# MCU.net
KiCad netlist of a schematic drawn in Altium Designer
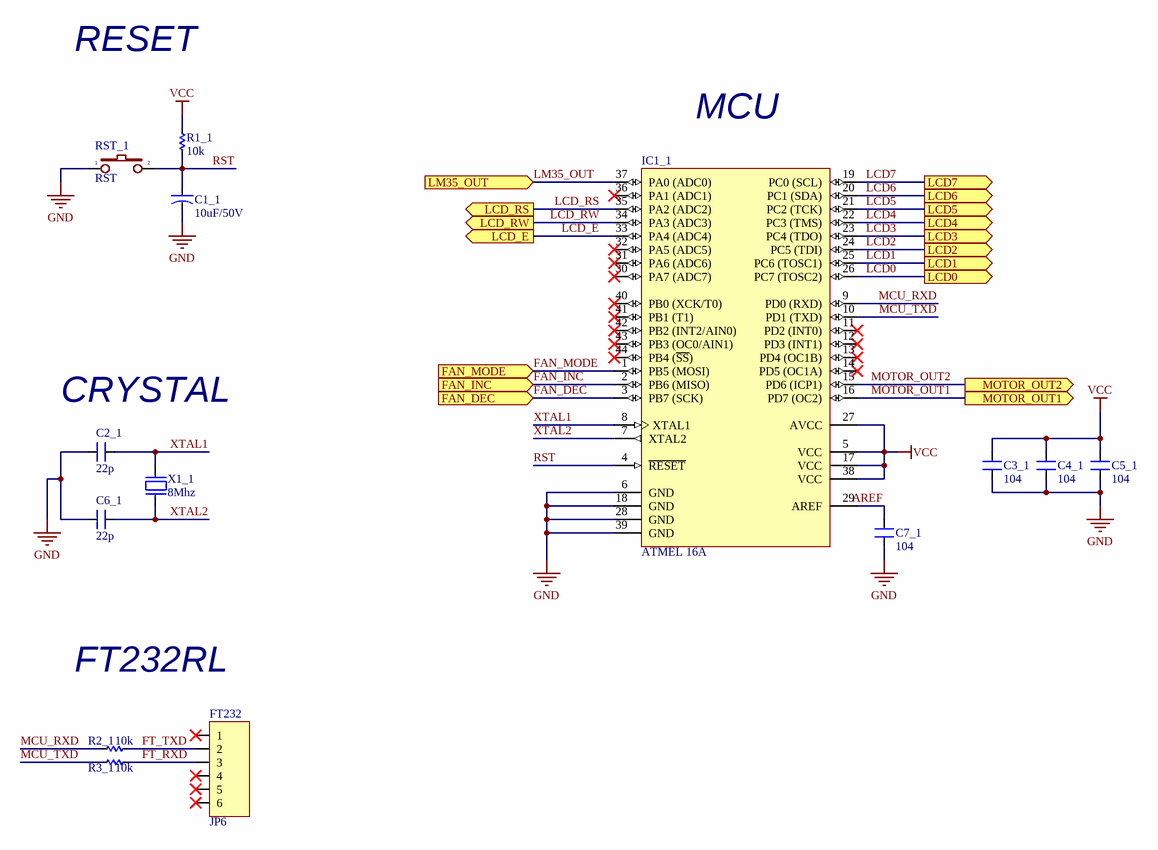
[diagram p0: MCU.SchDoc]

(export (version "E")
  (design (tool "Eeschema 10.0.6"))
  (components
    (comp (ref "C1_1")
      (value "10uF/50V")
      (footprint "CAP-ALU-SMD-5.5x5.5")
      (description "Polarized Capacitor (Axial)")
      (fields (field (name "PUBLISHER") "Altium Limited"))
      (libsource (lib "Altium Library") (part "CN-ALU-SMD"))
    )
    (comp (ref "C2_1") (value "22p") (footprint "CN-SMD-0805") (libsource (lib "Altium Library") (part "CN")))
    (comp (ref "C3_1") (value "104") (footprint "CN-SMD-0805") (libsource (lib "Altium Library") (part "CN")))
    (comp (ref "C4_1") (value "104") (footprint "CN-SMD-0805") (libsource (lib "Altium Library") (part "CN")))
    (comp (ref "C5_1") (value "104") (footprint "CN-SMD-0805") (libsource (lib "Altium Library") (part "CN")))
    (comp (ref "C6_1") (value "22p") (footprint "CN-SMD-0805") (libsource (lib "Altium Library") (part "CN")))
    (comp (ref "C7_1") (value "104") (footprint "CN-SMD-0805") (libsource (lib "Altium Library") (part "CN")))
    (comp (ref "FT232")
      (value "JP6")
      (footprint "JP6-C1T")
      (description "WR-PHD 2.54 mm Angled Socket Header")
      (fields
        (field (name "MANUFACTURER") "Würth Elektronik eiSos GmbH")
        (field (name "PARTNO") "613006143121")
        (field (name "CREATED BY") "Karrer Zheng")
      )
      (libsource (lib "Altium Library") (part "JP6"))
    )
    (comp (ref "IC1_1")
      (value "ATMEL 16A")
      (footprint "TQFP44")
      (libsource (lib "Altium Library") (part "ATmega16A-AU"))
    )
    (comp (ref "R1_1")
      (value "10k")
      (footprint "RES-SMD-0805")
      (description "Resistor")
      (fields
        (field (name "MANUFACTURER") "Generic Components")
        (field (name "PUBLISHER") "Altium Hobart Technology Centre")
      )
      (libsource (lib "Altium Library") (part "Res-SMD"))
    )
    (comp (ref "R2_1")
      (value "10k")
      (footprint "RES-SMD-0805")
      (description "Resistor")
      (fields
        (field (name "MANUFACTURER") "Generic Components")
        (field (name "PUBLISHER") "Altium Hobart Technology Centre")
      )
      (libsource (lib "Altium Library") (part "Res-SMD"))
    )
    (comp (ref "R3_1")
      (value "10k")
      (footprint "RES-SMD-0805")
      (description "Resistor")
      (fields
        (field (name "MANUFACTURER") "Generic Components")
        (field (name "PUBLISHER") "Altium Hobart Technology Centre")
      )
      (libsource (lib "Altium Library") (part "Res-SMD"))
    )
    (comp (ref "RST_1")
      (value "RST")
      (footprint "SW1-SMD")
      (description "Switch button 2 pin")
      (libsource (lib "Altium Library") (part "SW2"))
    )
    (comp (ref "X1_1")
      (value "8Mhz")
      (footprint "XT2")
      (description "Crystal, 32.768 KHz, -40 to 85 degC, 3.2 x 1.5 x 0.9 mm SMD")
      (libsource (lib "Altium Library") (part "XT2"))
    )
  )
  (nets
    (net (code "1") (name "/AREF") (class "Default")
      (node (ref "C7_1") (pin "2") (pinfunction "2_2") (pintype "passive"))
      (node (ref "IC1_1") (pin "29") (pinfunction "AREF_29") (pintype "power_in"))
    )
    (net (code "2") (name "/FAN_DEC") (class "Default")
      (node (ref "IC1_1") (pin "3") (pinfunction "PB7_(SCK)_3") (pintype "bidirectional"))
    )
    (net (code "3") (name "/FAN_INC") (class "Default")
      (node (ref "IC1_1") (pin "2") (pinfunction "PB6_(MISO)_2") (pintype "bidirectional"))
    )
    (net (code "4") (name "/FAN_MODE") (class "Default")
      (node (ref "IC1_1") (pin "1") (pinfunction "PB5_(MOSI)_1") (pintype "bidirectional"))
    )
    (net (code "5") (name "/FT_RXD") (class "Default")
      (node (ref "FT232") (pin "3") (pinfunction "3_3") (pintype "passive"))
      (node (ref "R3_1") (pin "1") (pinfunction "1_1") (pintype "passive"))
    )
    (net (code "6") (name "/FT_TXD") (class "Default")
      (node (ref "FT232") (pin "2") (pinfunction "2_2") (pintype "passive"))
      (node (ref "R2_1") (pin "1") (pinfunction "1_1") (pintype "passive"))
    )
    (net (code "7") (name "/LCD0") (class "Default")
      (node (ref "IC1_1") (pin "26") (pinfunction "PC7_(TOSC2)_26") (pintype "bidirectional"))
    )
    (net (code "8") (name "/LCD1") (class "Default")
      (node (ref "IC1_1") (pin "25") (pinfunction "PC6_(TOSC1)_25") (pintype "bidirectional"))
    )
    (net (code "9") (name "/LCD2") (class "Default")
      (node (ref "IC1_1") (pin "24") (pinfunction "PC5_(TDI)_24") (pintype "bidirectional"))
    )
    (net (code "10") (name "/LCD3") (class "Default")
      (node (ref "IC1_1") (pin "23") (pinfunction "PC4_(TDO)_23") (pintype "bidirectional"))
    )
    (net (code "11") (name "/LCD4") (class "Default")
      (node (ref "IC1_1") (pin "22") (pinfunction "PC3_(TMS)_22") (pintype "bidirectional"))
    )
    (net (code "12") (name "/LCD5") (class "Default")
      (node (ref "IC1_1") (pin "21") (pinfunction "PC2_(TCK)_21") (pintype "bidirectional"))
    )
    (net (code "13") (name "/LCD6") (class "Default")
      (node (ref "IC1_1") (pin "20") (pinfunction "PC1_(SDA)_20") (pintype "bidirectional"))
    )
    (net (code "14") (name "/LCD7") (class "Default")
      (node (ref "IC1_1") (pin "19") (pinfunction "PC0_(SCL)_19") (pintype "bidirectional"))
    )
    (net (code "15") (name "/LCD_E") (class "Default")
      (node (ref "IC1_1") (pin "33") (pinfunction "PA4_(ADC4)_33") (pintype "bidirectional"))
    )
    (net (code "16") (name "/LCD_RS") (class "Default")
      (node (ref "IC1_1") (pin "35") (pinfunction "PA2_(ADC2)_35") (pintype "bidirectional"))
    )
    (net (code "17") (name "/LCD_RW") (class "Default")
      (node (ref "IC1_1") (pin "34") (pinfunction "PA3_(ADC3)_34") (pintype "bidirectional"))
    )
    (net (code "18") (name "/LM35_OUT") (class "Default")
      (node (ref "IC1_1") (pin "37") (pinfunction "PA0_(ADC0)_37") (pintype "bidirectional"))
    )
    (net (code "19") (name "/MCU_RXD") (class "Default")
      (node (ref "IC1_1") (pin "9") (pinfunction "PD0_(RXD)_9") (pintype "bidirectional"))
      (node (ref "R2_1") (pin "2") (pinfunction "2_2") (pintype "passive"))
    )
    (net (code "20") (name "/MCU_TXD") (class "Default")
      (node (ref "IC1_1") (pin "10") (pinfunction "PD1_(TXD)_10") (pintype "bidirectional"))
      (node (ref "R3_1") (pin "2") (pinfunction "2_2") (pintype "passive"))
    )
    (net (code "21") (name "/MOTOR_OUT1") (class "Default")
      (node (ref "IC1_1") (pin "16") (pinfunction "PD7_(OC2)_16") (pintype "bidirectional"))
    )
    (net (code "22") (name "/MOTOR_OUT2") (class "Default")
      (node (ref "IC1_1") (pin "15") (pinfunction "PD6_(ICP1)_15") (pintype "bidirectional"))
    )
    (net (code "23") (name "/RST") (class "Default")
      (node (ref "C1_1") (pin "1") (pinfunction "1_1") (pintype "passive"))
      (node (ref "IC1_1") (pin "4") (pinfunction "~{RESET}_4") (pintype "input"))
      (node (ref "R1_1") (pin "2") (pinfunction "2_2") (pintype "passive"))
      (node (ref "RST_1") (pin "2") (pinfunction "2_2") (pintype "passive"))
    )
    (net (code "24") (name "/XTAL1") (class "Default")
      (node (ref "C2_1") (pin "1") (pinfunction "1_1") (pintype "passive"))
      (node (ref "IC1_1") (pin "8") (pinfunction "XTAL1_8") (pintype "input"))
      (node (ref "X1_1") (pin "2") (pinfunction "2_2") (pintype "passive"))
    )
    (net (code "25") (name "/XTAL2") (class "Default")
      (node (ref "C6_1") (pin "1") (pinfunction "1_1") (pintype "passive"))
      (node (ref "IC1_1") (pin "7") (pinfunction "XTAL2_7") (pintype "output"))
      (node (ref "X1_1") (pin "1") (pinfunction "1_1") (pintype "passive"))
    )
    (net (code "26") (name "GND") (class "Default")
      (node (ref "C1_1") (pin "2") (pinfunction "2_2") (pintype "passive"))
      (node (ref "C2_1") (pin "2") (pinfunction "2_2") (pintype "passive"))
      (node (ref "C3_1") (pin "1") (pinfunction "1_1") (pintype "passive"))
      (node (ref "C4_1") (pin "1") (pinfunction "1_1") (pintype "passive"))
      (node (ref "C5_1") (pin "1") (pinfunction "1_1") (pintype "passive"))
      (node (ref "C6_1") (pin "2") (pinfunction "2_2") (pintype "passive"))
      (node (ref "C7_1") (pin "1") (pinfunction "1_1") (pintype "passive"))
      (node (ref "IC1_1") (pin "18") (pinfunction "GND_18") (pintype "power_in"))
      (node (ref "IC1_1") (pin "28") (pinfunction "GND_28") (pintype "power_in"))
      (node (ref "IC1_1") (pin "39") (pinfunction "GND_39") (pintype "power_in"))
      (node (ref "IC1_1") (pin "6") (pinfunction "GND_6") (pintype "power_in"))
      (node (ref "RST_1") (pin "1") (pinfunction "1_1") (pintype "passive"))
    )
    (net (code "27") (name "VCC") (class "Default")
      (node (ref "C3_1") (pin "2") (pinfunction "2_2") (pintype "passive"))
      (node (ref "C4_1") (pin "2") (pinfunction "2_2") (pintype "passive"))
      (node (ref "C5_1") (pin "2") (pinfunction "2_2") (pintype "passive"))
      (node (ref "IC1_1") (pin "17") (pinfunction "VCC_17") (pintype "power_in"))
      (node (ref "IC1_1") (pin "27") (pinfunction "AVCC_27") (pintype "power_in"))
      (node (ref "IC1_1") (pin "38") (pinfunction "VCC_38") (pintype "power_in"))
      (node (ref "IC1_1") (pin "5") (pinfunction "VCC_5") (pintype "power_in"))
      (node (ref "R1_1") (pin "1") (pinfunction "1_1") (pintype "passive"))
    )
    (net (code "28") (name "unconnected-(FT232-Pad1)") (class "Default")
      (node (ref "FT232") (pin "1") (pinfunction "1_1") (pintype "passive+no_connect"))
    )
    (net (code "29") (name "unconnected-(FT232-Pad4)") (class "Default")
      (node (ref "FT232") (pin "4") (pinfunction "4_4") (pintype "passive+no_connect"))
    )
    (net (code "30") (name "unconnected-(FT232-Pad5)") (class "Default")
      (node (ref "FT232") (pin "5") (pinfunction "5_5") (pintype "passive+no_connect"))
    )
    (net (code "31") (name "unconnected-(FT232-Pad6)") (class "Default")
      (node (ref "FT232") (pin "6") (pinfunction "6_6") (pintype "passive+no_connect"))
    )
    (net (code "32") (name "unconnected-(IC1_1-PA1_(ADC1)-Pad36)") (class "Default")
      (node (ref "IC1_1") (pin "36") (pinfunction "PA1_(ADC1)_36") (pintype "bidirectional+no_connect"))
    )
    (net (code "33") (name "unconnected-(IC1_1-PA5_(ADC5)-Pad32)") (class "Default")
      (node (ref "IC1_1") (pin "32") (pinfunction "PA5_(ADC5)_32") (pintype "bidirectional+no_connect"))
    )
    (net (code "34") (name "unconnected-(IC1_1-PA6_(ADC6)-Pad31)") (class "Default")
      (node (ref "IC1_1") (pin "31") (pinfunction "PA6_(ADC6)_31") (pintype "bidirectional+no_connect"))
    )
    (net (code "35") (name "unconnected-(IC1_1-PA7_(ADC7)-Pad30)") (class "Default")
      (node (ref "IC1_1") (pin "30") (pinfunction "PA7_(ADC7)_30") (pintype "bidirectional+no_connect"))
    )
    (net (code "36") (name "unconnected-(IC1_1-PB0_(XCK{slash}T0)-Pad40)") (class "Default")
      (node (ref "IC1_1") (pin "40") (pinfunction "PB0_(XCK/T0)_40") (pintype "bidirectional+no_connect"))
    )
    (net (code "37") (name "unconnected-(IC1_1-PB1_(T1)-Pad41)") (class "Default")
      (node (ref "IC1_1") (pin "41") (pinfunction "PB1_(T1)_41") (pintype "bidirectional+no_connect"))
    )
    (net (code "38") (name "unconnected-(IC1_1-PB2_(INT2{slash}AIN0)-Pad42)") (class "Default")
      (node (ref "IC1_1") (pin "42") (pinfunction "PB2_(INT2/AIN0)_42") (pintype "bidirectional+no_connect"))
    )
    (net (code "39") (name "unconnected-(IC1_1-PB3_(OC0{slash}AIN1)-Pad43)") (class "Default")
      (node (ref "IC1_1") (pin "43") (pinfunction "PB3_(OC0/AIN1)_43") (pintype "bidirectional+no_connect"))
    )
    (net (code "40") (name "unconnected-(IC1_1-PB4_(~{SS})-Pad44)") (class "Default")
      (node (ref "IC1_1") (pin "44") (pinfunction "PB4_(~{SS})_44") (pintype "bidirectional+no_connect"))
    )
    (net (code "41") (name "unconnected-(IC1_1-PD2_(INT0)-Pad11)") (class "Default")
      (node (ref "IC1_1") (pin "11") (pinfunction "PD2_(INT0)_11") (pintype "bidirectional+no_connect"))
    )
    (net (code "42") (name "unconnected-(IC1_1-PD3_(INT1)-Pad12)") (class "Default")
      (node (ref "IC1_1") (pin "12") (pinfunction "PD3_(INT1)_12") (pintype "bidirectional+no_connect"))
    )
    (net (code "43") (name "unconnected-(IC1_1-PD4_(OC1B)-Pad13)") (class "Default")
      (node (ref "IC1_1") (pin "13") (pinfunction "PD4_(OC1B)_13") (pintype "bidirectional+no_connect"))
    )
    (net (code "44") (name "unconnected-(IC1_1-PD5_(OC1A)-Pad14)") (class "Default")
      (node (ref "IC1_1") (pin "14") (pinfunction "PD5_(OC1A)_14") (pintype "bidirectional+no_connect"))
    )
  )
)
